# Lampen.net
KiCad netlist of a schematic drawn in EAGLE
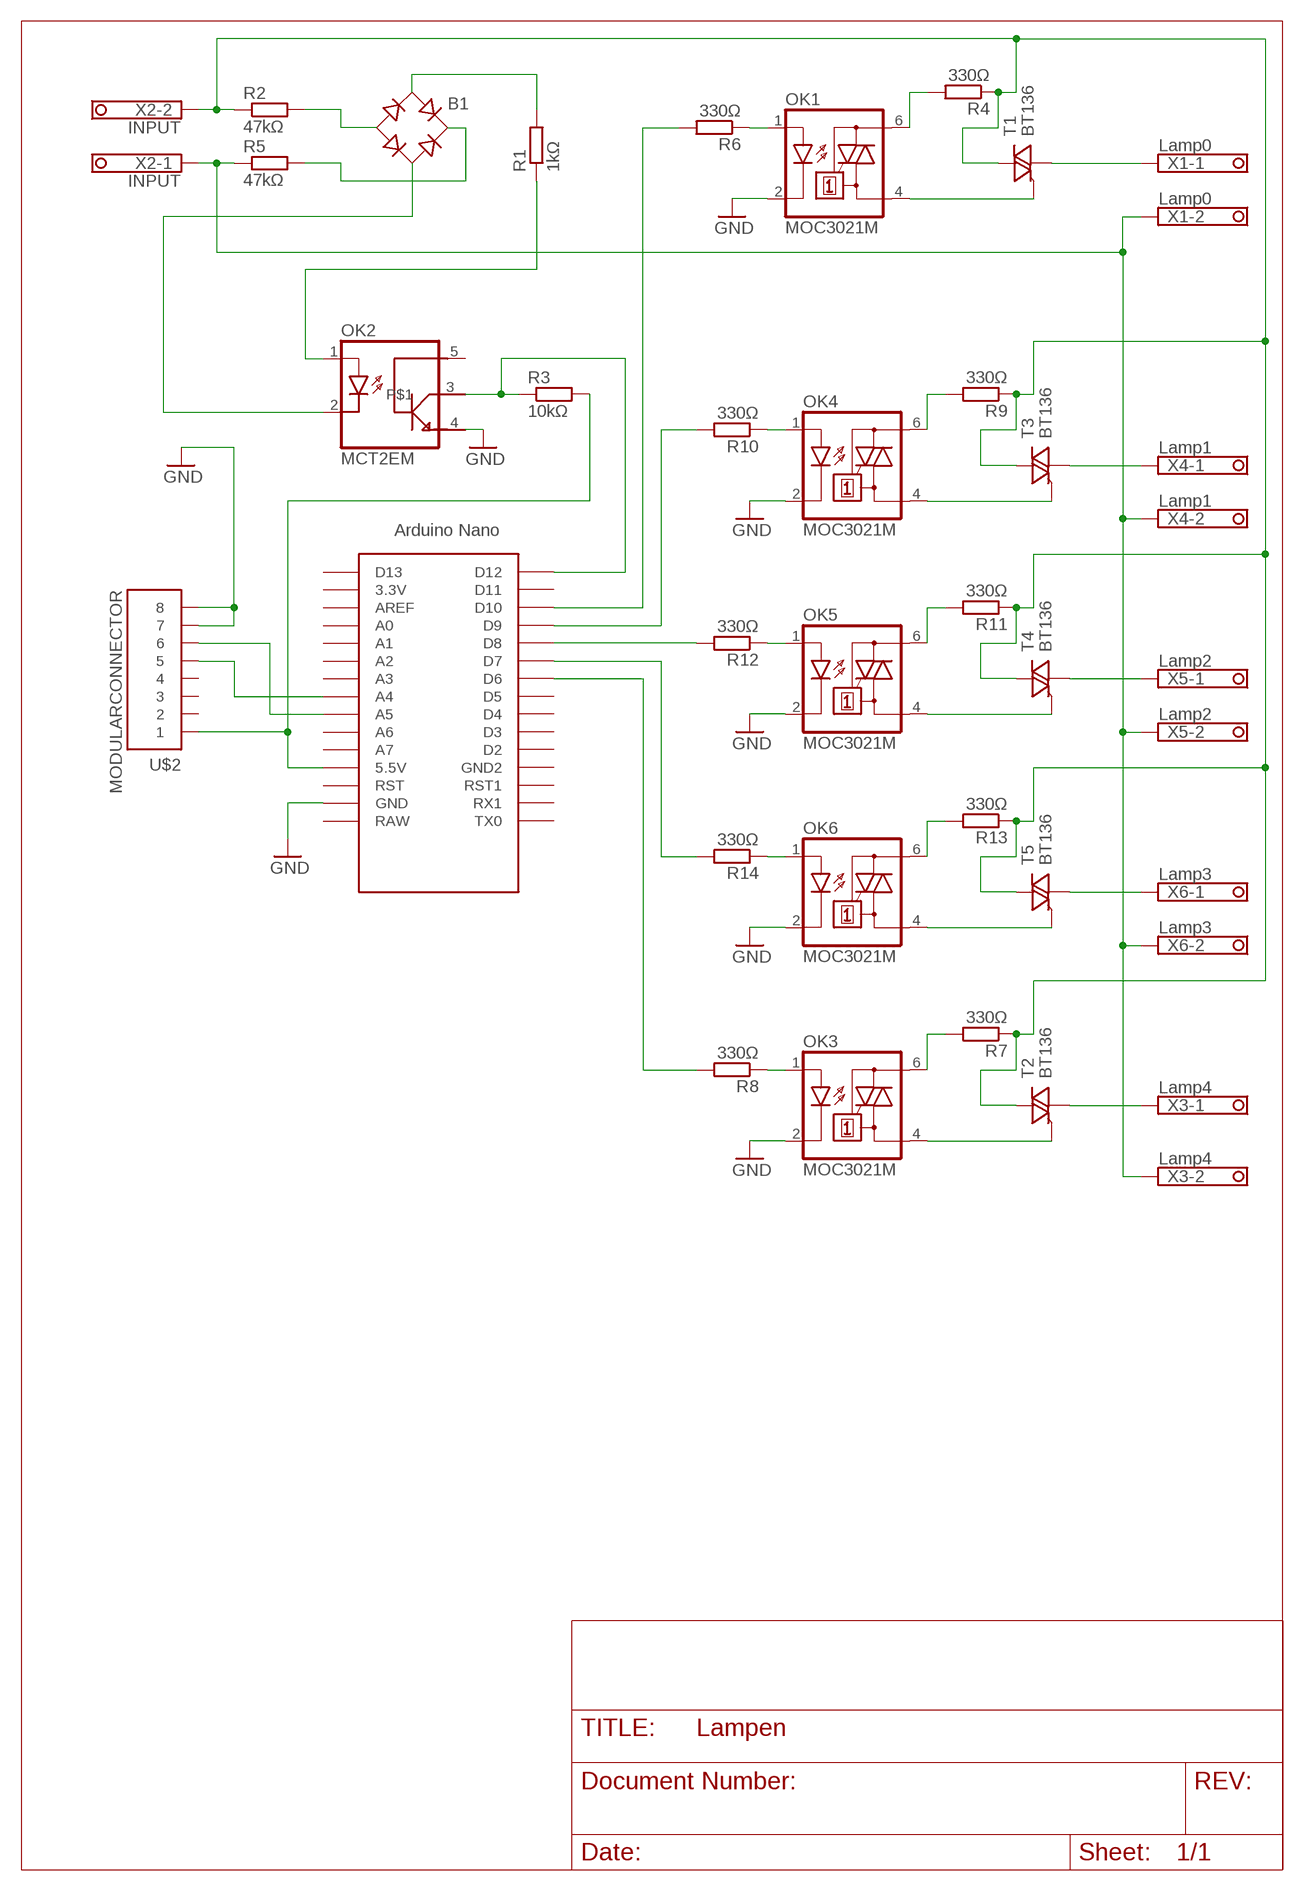
[diagram p0: schematic, sheet 1]

(export (version "E")
  (design (tool "Eeschema 10.0.6"))
  (components
    (comp (ref "B1")
      (value "B250C1500G")
      (footprint "eagle-import:RB1A")
      (libsource (lib "eagle-import") (part "B250C1500G"))
    )
    (comp (ref "OK1")
      (value "MOC3021M")
      (footprint "eagle-import:DIL06")
      (fields (field (name "MF") "FAIRCHILD SEMICONDUCTOR") (field (name "MPN") "MOC3010-M"))
      (libsource (lib "eagle-import") (part "MOC3021M10"))
    )
    (comp (ref "OK2")
      (value "MCT2EM")
      (footprint "eagle-import:DIL06")
      (fields (field (name "MF") "FAIRCHILD SEMICONDUCTOR") (field (name "MPN") "MOC3021-M"))
      (libsource (lib "eagle-import") (part "MCT2EM21"))
    )
    (comp (ref "OK3")
      (value "MOC3021M")
      (footprint "eagle-import:DIL06")
      (fields (field (name "MF") "FAIRCHILD SEMICONDUCTOR") (field (name "MPN") "MOC3010-M"))
      (libsource (lib "eagle-import") (part "MOC3021M10"))
    )
    (comp (ref "OK4")
      (value "MOC3021M")
      (footprint "eagle-import:DIL06")
      (fields (field (name "MF") "FAIRCHILD SEMICONDUCTOR") (field (name "MPN") "MOC3010-M"))
      (libsource (lib "eagle-import") (part "MOC3021M10"))
    )
    (comp (ref "OK5")
      (value "MOC3021M")
      (footprint "eagle-import:DIL06")
      (fields (field (name "MF") "FAIRCHILD SEMICONDUCTOR") (field (name "MPN") "MOC3010-M"))
      (libsource (lib "eagle-import") (part "MOC3021M10"))
    )
    (comp (ref "OK6")
      (value "MOC3021M")
      (footprint "eagle-import:DIL06")
      (fields (field (name "MF") "FAIRCHILD SEMICONDUCTOR") (field (name "MPN") "MOC3010-M"))
      (libsource (lib "eagle-import") (part "MOC3021M10"))
    )
    (comp (ref "R1")
      (value "1kΩ")
      (footprint "eagle-import:M1206")
      (libsource (lib "eagle-import") (part "R-EU_M1206"))
    )
    (comp (ref "R2")
      (value "47kΩ")
      (footprint "eagle-import:R2512")
      (libsource (lib "eagle-import") (part "R-EU_R2512"))
    )
    (comp (ref "R3")
      (value "10kΩ")
      (footprint "eagle-import:M1206")
      (libsource (lib "eagle-import") (part "R-EU_M1206"))
    )
    (comp (ref "R4")
      (value "330Ω")
      (footprint "eagle-import:M1206")
      (libsource (lib "eagle-import") (part "R-EU_M1206"))
    )
    (comp (ref "R5")
      (value "47kΩ")
      (footprint "eagle-import:R2512")
      (libsource (lib "eagle-import") (part "R-EU_R2512"))
    )
    (comp (ref "R6")
      (value "330Ω")
      (footprint "eagle-import:M1206")
      (libsource (lib "eagle-import") (part "R-EU_M1206"))
    )
    (comp (ref "R7")
      (value "330Ω")
      (footprint "eagle-import:M1206")
      (libsource (lib "eagle-import") (part "R-EU_M1206"))
    )
    (comp (ref "R8")
      (value "330Ω")
      (footprint "eagle-import:M1206")
      (libsource (lib "eagle-import") (part "R-EU_M1206"))
    )
    (comp (ref "R9")
      (value "330Ω")
      (footprint "eagle-import:M1206")
      (libsource (lib "eagle-import") (part "R-EU_M1206"))
    )
    (comp (ref "R10")
      (value "330Ω")
      (footprint "eagle-import:M1206")
      (libsource (lib "eagle-import") (part "R-EU_M1206"))
    )
    (comp (ref "R11")
      (value "330Ω")
      (footprint "eagle-import:M1206")
      (libsource (lib "eagle-import") (part "R-EU_M1206"))
    )
    (comp (ref "R12")
      (value "330Ω")
      (footprint "eagle-import:M1206")
      (libsource (lib "eagle-import") (part "R-EU_M1206"))
    )
    (comp (ref "R13")
      (value "330Ω")
      (footprint "eagle-import:M1206")
      (libsource (lib "eagle-import") (part "R-EU_M1206"))
    )
    (comp (ref "R14")
      (value "330Ω")
      (footprint "eagle-import:M1206")
      (libsource (lib "eagle-import") (part "R-EU_M1206"))
    )
    (comp (ref "T1")
      (value "BT136")
      (footprint "eagle-import:TO220DS")
      (libsource (lib "eagle-import") (part "BT136"))
    )
    (comp (ref "T2")
      (value "BT136")
      (footprint "eagle-import:TO220DS")
      (libsource (lib "eagle-import") (part "BT136"))
    )
    (comp (ref "T3")
      (value "BT136")
      (footprint "eagle-import:TO220DS")
      (libsource (lib "eagle-import") (part "BT136"))
    )
    (comp (ref "T4")
      (value "BT136")
      (footprint "eagle-import:TO220DS")
      (libsource (lib "eagle-import") (part "BT136"))
    )
    (comp (ref "T5")
      (value "BT136")
      (footprint "eagle-import:TO220DS")
      (libsource (lib "eagle-import") (part "BT136"))
    )
    (comp (ref "U$1")
      (value "NANO")
      (footprint "eagle-import:NANO")
      (libsource (lib "eagle-import") (part "NANO"))
    )
    (comp (ref "U$2")
      (value "MODULARCONNECTOR")
      (footprint "eagle-import:MA04-2")
      (libsource (lib "eagle-import") (part "MODULARCONNECTOR"))
    )
    (comp (ref "X1")
      (value "Lamp0")
      (footprint "eagle-import:1751248")
      (libsource (lib "eagle-import") (part "1751248"))
    )
    (comp (ref "X2")
      (value "INPUT")
      (footprint "eagle-import:1751248")
      (libsource (lib "eagle-import") (part "1751248"))
    )
    (comp (ref "X3")
      (value "Lamp4")
      (footprint "eagle-import:1751248")
      (libsource (lib "eagle-import") (part "1751248"))
    )
    (comp (ref "X4")
      (value "Lamp1")
      (footprint "eagle-import:1751248")
      (libsource (lib "eagle-import") (part "1751248"))
    )
    (comp (ref "X5")
      (value "Lamp2")
      (footprint "eagle-import:1751248")
      (libsource (lib "eagle-import") (part "1751248"))
    )
    (comp (ref "X6")
      (value "Lamp3")
      (footprint "eagle-import:1751248")
      (libsource (lib "eagle-import") (part "1751248"))
    )
  )
  (nets
    (net (code "1") (name "GND") (class "Default")
      (node (ref "OK1") (pin "2") (pinfunction "C_2") (pintype "passive"))
      (node (ref "OK2") (pin "4") (pinfunction "A1_4") (pintype "passive"))
      (node (ref "OK3") (pin "2") (pinfunction "C_2") (pintype "passive"))
      (node (ref "OK4") (pin "2") (pinfunction "C_2") (pintype "passive"))
      (node (ref "OK5") (pin "2") (pinfunction "C_2") (pintype "passive"))
      (node (ref "OK6") (pin "2") (pinfunction "C_2") (pintype "passive"))
      (node (ref "U$1") (pin "GND") (pinfunction "GND_GND") (pintype "bidirectional"))
      (node (ref "U$2") (pin "7") (pinfunction "7_7") (pintype "input"))
      (node (ref "U$2") (pin "8") (pinfunction "8_8") (pintype "input"))
    )
    (net (code "2") (name "Net-(B1-Pad+)") (class "Default")
      (node (ref "B1") (pin "+") (pinfunction "+_+") (pintype "passive"))
      (node (ref "R5") (pin "2") (pinfunction "2_2") (pintype "passive"))
    )
    (net (code "3") (name "Net-(B1-Pad-)") (class "Default")
      (node (ref "B1") (pin "-") (pinfunction "-_-") (pintype "passive"))
      (node (ref "R2") (pin "2") (pinfunction "2_2") (pintype "passive"))
    )
    (net (code "4") (name "Net-(B1-PadAC1)") (class "Default")
      (node (ref "B1") (pin "AC1") (pinfunction "AC1_AC1") (pintype "passive"))
      (node (ref "R1") (pin "2") (pinfunction "2_2") (pintype "passive"))
    )
    (net (code "5") (name "Net-(OK1-A)") (class "Default")
      (node (ref "OK1") (pin "1") (pinfunction "A_1") (pintype "passive"))
      (node (ref "R6") (pin "1") (pinfunction "1_1") (pintype "passive"))
    )
    (net (code "6") (name "Net-(OK1-A1)") (class "Default")
      (node (ref "OK1") (pin "4") (pinfunction "A1_4") (pintype "passive"))
      (node (ref "T1") (pin "G") (pinfunction "G_G") (pintype "passive"))
    )
    (net (code "7") (name "Net-(OK1-A2)") (class "Default")
      (node (ref "OK1") (pin "6") (pinfunction "A2_6") (pintype "passive"))
      (node (ref "R4") (pin "2") (pinfunction "2_2") (pintype "passive"))
    )
    (net (code "8") (name "Net-(OK2-A)") (class "Default")
      (node (ref "OK2") (pin "1") (pinfunction "A_1") (pintype "passive"))
      (node (ref "R1") (pin "1") (pinfunction "1_1") (pintype "passive"))
    )
    (net (code "9") (name "Net-(OK2-C)") (class "Default")
      (node (ref "B1") (pin "AC2") (pinfunction "AC2_AC2") (pintype "passive"))
      (node (ref "OK2") (pin "2") (pinfunction "C_2") (pintype "passive"))
    )
    (net (code "10") (name "Net-(OK2-P$1)") (class "Default")
      (node (ref "OK2") (pin "3") (pinfunction "P$1_3") (pintype "bidirectional"))
      (node (ref "R3") (pin "1") (pinfunction "1_1") (pintype "passive"))
      (node (ref "U$1") (pin "D12") (pinfunction "D12_D12") (pintype "bidirectional"))
    )
    (net (code "11") (name "Net-(OK3-A)") (class "Default")
      (node (ref "OK3") (pin "1") (pinfunction "A_1") (pintype "passive"))
      (node (ref "R8") (pin "1") (pinfunction "1_1") (pintype "passive"))
    )
    (net (code "12") (name "Net-(OK3-A1)") (class "Default")
      (node (ref "OK3") (pin "4") (pinfunction "A1_4") (pintype "passive"))
      (node (ref "T2") (pin "G") (pinfunction "G_G") (pintype "passive"))
    )
    (net (code "13") (name "Net-(OK3-A2)") (class "Default")
      (node (ref "OK3") (pin "6") (pinfunction "A2_6") (pintype "passive"))
      (node (ref "R7") (pin "2") (pinfunction "2_2") (pintype "passive"))
    )
    (net (code "14") (name "Net-(OK4-A)") (class "Default")
      (node (ref "OK4") (pin "1") (pinfunction "A_1") (pintype "passive"))
      (node (ref "R10") (pin "1") (pinfunction "1_1") (pintype "passive"))
    )
    (net (code "15") (name "Net-(OK4-A1)") (class "Default")
      (node (ref "OK4") (pin "4") (pinfunction "A1_4") (pintype "passive"))
      (node (ref "T3") (pin "G") (pinfunction "G_G") (pintype "passive"))
    )
    (net (code "16") (name "Net-(OK4-A2)") (class "Default")
      (node (ref "OK4") (pin "6") (pinfunction "A2_6") (pintype "passive"))
      (node (ref "R9") (pin "2") (pinfunction "2_2") (pintype "passive"))
    )
    (net (code "17") (name "Net-(OK5-A)") (class "Default")
      (node (ref "OK5") (pin "1") (pinfunction "A_1") (pintype "passive"))
      (node (ref "R12") (pin "1") (pinfunction "1_1") (pintype "passive"))
    )
    (net (code "18") (name "Net-(OK5-A1)") (class "Default")
      (node (ref "OK5") (pin "4") (pinfunction "A1_4") (pintype "passive"))
      (node (ref "T4") (pin "G") (pinfunction "G_G") (pintype "passive"))
    )
    (net (code "19") (name "Net-(OK5-A2)") (class "Default")
      (node (ref "OK5") (pin "6") (pinfunction "A2_6") (pintype "passive"))
      (node (ref "R11") (pin "2") (pinfunction "2_2") (pintype "passive"))
    )
    (net (code "20") (name "Net-(OK6-A)") (class "Default")
      (node (ref "OK6") (pin "1") (pinfunction "A_1") (pintype "passive"))
      (node (ref "R14") (pin "1") (pinfunction "1_1") (pintype "passive"))
    )
    (net (code "21") (name "Net-(OK6-A1)") (class "Default")
      (node (ref "OK6") (pin "4") (pinfunction "A1_4") (pintype "passive"))
      (node (ref "T5") (pin "G") (pinfunction "G_G") (pintype "passive"))
    )
    (net (code "22") (name "Net-(OK6-A2)") (class "Default")
      (node (ref "OK6") (pin "6") (pinfunction "A2_6") (pintype "passive"))
      (node (ref "R13") (pin "2") (pinfunction "2_2") (pintype "passive"))
    )
    (net (code "23") (name "Net-(R6-Pad2)") (class "Default")
      (node (ref "R6") (pin "2") (pinfunction "2_2") (pintype "passive"))
      (node (ref "U$1") (pin "D10") (pinfunction "D10_D10") (pintype "bidirectional"))
    )
    (net (code "24") (name "Net-(R8-Pad2)") (class "Default")
      (node (ref "R8") (pin "2") (pinfunction "2_2") (pintype "passive"))
      (node (ref "U$1") (pin "D6") (pinfunction "D6_D6") (pintype "bidirectional"))
    )
    (net (code "25") (name "Net-(R10-Pad2)") (class "Default")
      (node (ref "R10") (pin "2") (pinfunction "2_2") (pintype "passive"))
      (node (ref "U$1") (pin "D9") (pinfunction "D9_D9") (pintype "bidirectional"))
    )
    (net (code "26") (name "Net-(R12-Pad2)") (class "Default")
      (node (ref "R12") (pin "2") (pinfunction "2_2") (pintype "passive"))
      (node (ref "U$1") (pin "D8") (pinfunction "D8_D8") (pintype "bidirectional"))
    )
    (net (code "27") (name "Net-(R14-Pad2)") (class "Default")
      (node (ref "R14") (pin "2") (pinfunction "2_2") (pintype "passive"))
      (node (ref "U$1") (pin "D7") (pinfunction "D7_D7") (pintype "bidirectional"))
    )
    (net (code "28") (name "Net-(U$1-5.5V)") (class "Default")
      (node (ref "R3") (pin "2") (pinfunction "2_2") (pintype "passive"))
      (node (ref "U$1") (pin "5V") (pinfunction "5.5V_5V") (pintype "bidirectional"))
      (node (ref "U$2") (pin "1") (pinfunction "1_1") (pintype "input"))
    )
    (net (code "29") (name "Net-(U$1-PadA4)") (class "Default")
      (node (ref "U$1") (pin "A4") (pinfunction "A4_A4") (pintype "bidirectional"))
      (node (ref "U$2") (pin "5") (pinfunction "5_5") (pintype "input"))
    )
    (net (code "30") (name "Net-(U$1-PadA5)") (class "Default")
      (node (ref "U$1") (pin "A5") (pinfunction "A5_A5") (pintype "bidirectional"))
      (node (ref "U$2") (pin "6") (pinfunction "6_6") (pintype "input"))
    )
    (net (code "31") (name "Net-(X1A-K)") (class "Default")
      (node (ref "T1") (pin "A1") (pinfunction "A1_A1") (pintype "passive"))
      (node (ref "X1") (pin "1") (pinfunction "K_1") (pintype "passive"))
    )
    (net (code "32") (name "Net-(X1B-K)") (class "Default")
      (node (ref "R5") (pin "1") (pinfunction "1_1") (pintype "passive"))
      (node (ref "X1") (pin "2") (pinfunction "K_2") (pintype "passive"))
      (node (ref "X2") (pin "1") (pinfunction "K_1") (pintype "passive"))
      (node (ref "X3") (pin "2") (pinfunction "K_2") (pintype "passive"))
      (node (ref "X4") (pin "2") (pinfunction "K_2") (pintype "passive"))
      (node (ref "X5") (pin "2") (pinfunction "K_2") (pintype "passive"))
      (node (ref "X6") (pin "2") (pinfunction "K_2") (pintype "passive"))
    )
    (net (code "33") (name "Net-(X2B-K)") (class "Default")
      (node (ref "R11") (pin "1") (pinfunction "1_1") (pintype "passive"))
      (node (ref "R13") (pin "1") (pinfunction "1_1") (pintype "passive"))
      (node (ref "R2") (pin "1") (pinfunction "1_1") (pintype "passive"))
      (node (ref "R4") (pin "1") (pinfunction "1_1") (pintype "passive"))
      (node (ref "R7") (pin "1") (pinfunction "1_1") (pintype "passive"))
      (node (ref "R9") (pin "1") (pinfunction "1_1") (pintype "passive"))
      (node (ref "T1") (pin "A2") (pinfunction "A2_A2") (pintype "passive"))
      (node (ref "T2") (pin "A2") (pinfunction "A2_A2") (pintype "passive"))
      (node (ref "T3") (pin "A2") (pinfunction "A2_A2") (pintype "passive"))
      (node (ref "T4") (pin "A2") (pinfunction "A2_A2") (pintype "passive"))
      (node (ref "T5") (pin "A2") (pinfunction "A2_A2") (pintype "passive"))
      (node (ref "X2") (pin "2") (pinfunction "K_2") (pintype "passive"))
    )
    (net (code "34") (name "Net-(X3A-K)") (class "Default")
      (node (ref "T2") (pin "A1") (pinfunction "A1_A1") (pintype "passive"))
      (node (ref "X3") (pin "1") (pinfunction "K_1") (pintype "passive"))
    )
    (net (code "35") (name "Net-(X4A-K)") (class "Default")
      (node (ref "T3") (pin "A1") (pinfunction "A1_A1") (pintype "passive"))
      (node (ref "X4") (pin "1") (pinfunction "K_1") (pintype "passive"))
    )
    (net (code "36") (name "Net-(X5A-K)") (class "Default")
      (node (ref "T4") (pin "A1") (pinfunction "A1_A1") (pintype "passive"))
      (node (ref "X5") (pin "1") (pinfunction "K_1") (pintype "passive"))
    )
    (net (code "37") (name "Net-(X6A-K)") (class "Default")
      (node (ref "T5") (pin "A1") (pinfunction "A1_A1") (pintype "passive"))
      (node (ref "X6") (pin "1") (pinfunction "K_1") (pintype "passive"))
    )
    (net (code "38") (name "unconnected-(OK2-A2-Pad5)") (class "Default")
      (node (ref "OK2") (pin "5") (pinfunction "A2_5") (pintype "passive"))
    )
    (net (code "39") (name "unconnected-(U$1-GND2-PadGND1)") (class "Default")
      (node (ref "U$1") (pin "GND1") (pinfunction "GND2_GND1") (pintype "bidirectional"))
    )
    (net (code "40") (name "unconnected-(U$1-Pad3.3V)") (class "Default")
      (node (ref "U$1") (pin "3.3V") (pinfunction "3.3V_3.3V") (pintype "bidirectional"))
    )
    (net (code "41") (name "unconnected-(U$1-PadA0)") (class "Default")
      (node (ref "U$1") (pin "A0") (pinfunction "A0_A0") (pintype "bidirectional"))
    )
    (net (code "42") (name "unconnected-(U$1-PadA1)") (class "Default")
      (node (ref "U$1") (pin "A1") (pinfunction "A1_A1") (pintype "bidirectional"))
    )
    (net (code "43") (name "unconnected-(U$1-PadA2)") (class "Default")
      (node (ref "U$1") (pin "A2") (pinfunction "A2_A2") (pintype "bidirectional"))
    )
    (net (code "44") (name "unconnected-(U$1-PadA3)") (class "Default")
      (node (ref "U$1") (pin "A3") (pinfunction "A3_A3") (pintype "bidirectional"))
    )
    (net (code "45") (name "unconnected-(U$1-PadA6)") (class "Default")
      (node (ref "U$1") (pin "A6") (pinfunction "A6_A6") (pintype "bidirectional"))
    )
    (net (code "46") (name "unconnected-(U$1-PadA7)") (class "Default")
      (node (ref "U$1") (pin "A7") (pinfunction "A7_A7") (pintype "bidirectional"))
    )
    (net (code "47") (name "unconnected-(U$1-PadAREF)") (class "Default")
      (node (ref "U$1") (pin "AREF") (pinfunction "AREF_AREF") (pintype "bidirectional"))
    )
    (net (code "48") (name "unconnected-(U$1-PadD2)") (class "Default")
      (node (ref "U$1") (pin "D2") (pinfunction "D2_D2") (pintype "bidirectional"))
    )
    (net (code "49") (name "unconnected-(U$1-PadD3)") (class "Default")
      (node (ref "U$1") (pin "D3") (pinfunction "D3_D3") (pintype "bidirectional"))
    )
    (net (code "50") (name "unconnected-(U$1-PadD4)") (class "Default")
      (node (ref "U$1") (pin "D4") (pinfunction "D4_D4") (pintype "bidirectional"))
    )
    (net (code "51") (name "unconnected-(U$1-PadD5)") (class "Default")
      (node (ref "U$1") (pin "D5") (pinfunction "D5_D5") (pintype "bidirectional"))
    )
    (net (code "52") (name "unconnected-(U$1-PadD11)") (class "Default")
      (node (ref "U$1") (pin "D11") (pinfunction "D11_D11") (pintype "bidirectional"))
    )
    (net (code "53") (name "unconnected-(U$1-PadD13)") (class "Default")
      (node (ref "U$1") (pin "D13") (pinfunction "D13_D13") (pintype "bidirectional"))
    )
    (net (code "54") (name "unconnected-(U$1-PadICSP1)") (class "Default")
      (node (ref "U$1") (pin "ICSP1") (pinfunction "ICSP1_ICSP1") (pintype "bidirectional"))
    )
    (net (code "55") (name "unconnected-(U$1-PadICSP2)") (class "Default")
      (node (ref "U$1") (pin "ICSP2") (pinfunction "ICSP2_ICSP2") (pintype "bidirectional"))
    )
    (net (code "56") (name "unconnected-(U$1-PadICSP3)") (class "Default")
      (node (ref "U$1") (pin "ICSP3") (pinfunction "ICSP3_ICSP3") (pintype "bidirectional"))
    )
    (net (code "57") (name "unconnected-(U$1-PadICSP4)") (class "Default")
      (node (ref "U$1") (pin "ICSP4") (pinfunction "ICSP4_ICSP4") (pintype "bidirectional"))
    )
    (net (code "58") (name "unconnected-(U$1-PadICSP5)") (class "Default")
      (node (ref "U$1") (pin "ICSP5") (pinfunction "ICSP5_ICSP5") (pintype "bidirectional"))
    )
    (net (code "59") (name "unconnected-(U$1-PadICSP6)") (class "Default")
      (node (ref "U$1") (pin "ICSP6") (pinfunction "ICSP6_ICSP6") (pintype "bidirectional"))
    )
    (net (code "60") (name "unconnected-(U$1-PadRAW)") (class "Default")
      (node (ref "U$1") (pin "RAW") (pinfunction "RAW_RAW") (pintype "bidirectional"))
    )
    (net (code "61") (name "unconnected-(U$1-PadRST)") (class "Default")
      (node (ref "U$1") (pin "RST") (pinfunction "RST_RST") (pintype "bidirectional"))
    )
    (net (code "62") (name "unconnected-(U$1-PadRST1)") (class "Default")
      (node (ref "U$1") (pin "RST1") (pinfunction "RST1_RST1") (pintype "bidirectional"))
    )
    (net (code "63") (name "unconnected-(U$1-PadRX1)") (class "Default")
      (node (ref "U$1") (pin "RX1") (pinfunction "RX1_RX1") (pintype "bidirectional"))
    )
    (net (code "64") (name "unconnected-(U$1-PadTX0)") (class "Default")
      (node (ref "U$1") (pin "TX0") (pinfunction "TX0_TX0") (pintype "bidirectional"))
    )
    (net (code "65") (name "unconnected-(U$2-Pad2)") (class "Default")
      (node (ref "U$2") (pin "2") (pinfunction "2_2") (pintype "input"))
    )
    (net (code "66") (name "unconnected-(U$2-Pad3)") (class "Default")
      (node (ref "U$2") (pin "3") (pinfunction "3_3") (pintype "input"))
    )
    (net (code "67") (name "unconnected-(U$2-Pad4)") (class "Default")
      (node (ref "U$2") (pin "4") (pinfunction "4_4") (pintype "input"))
    )
  )
)
